# LEDs_Switches.net
KiCad netlist of a schematic drawn in Altium Designer
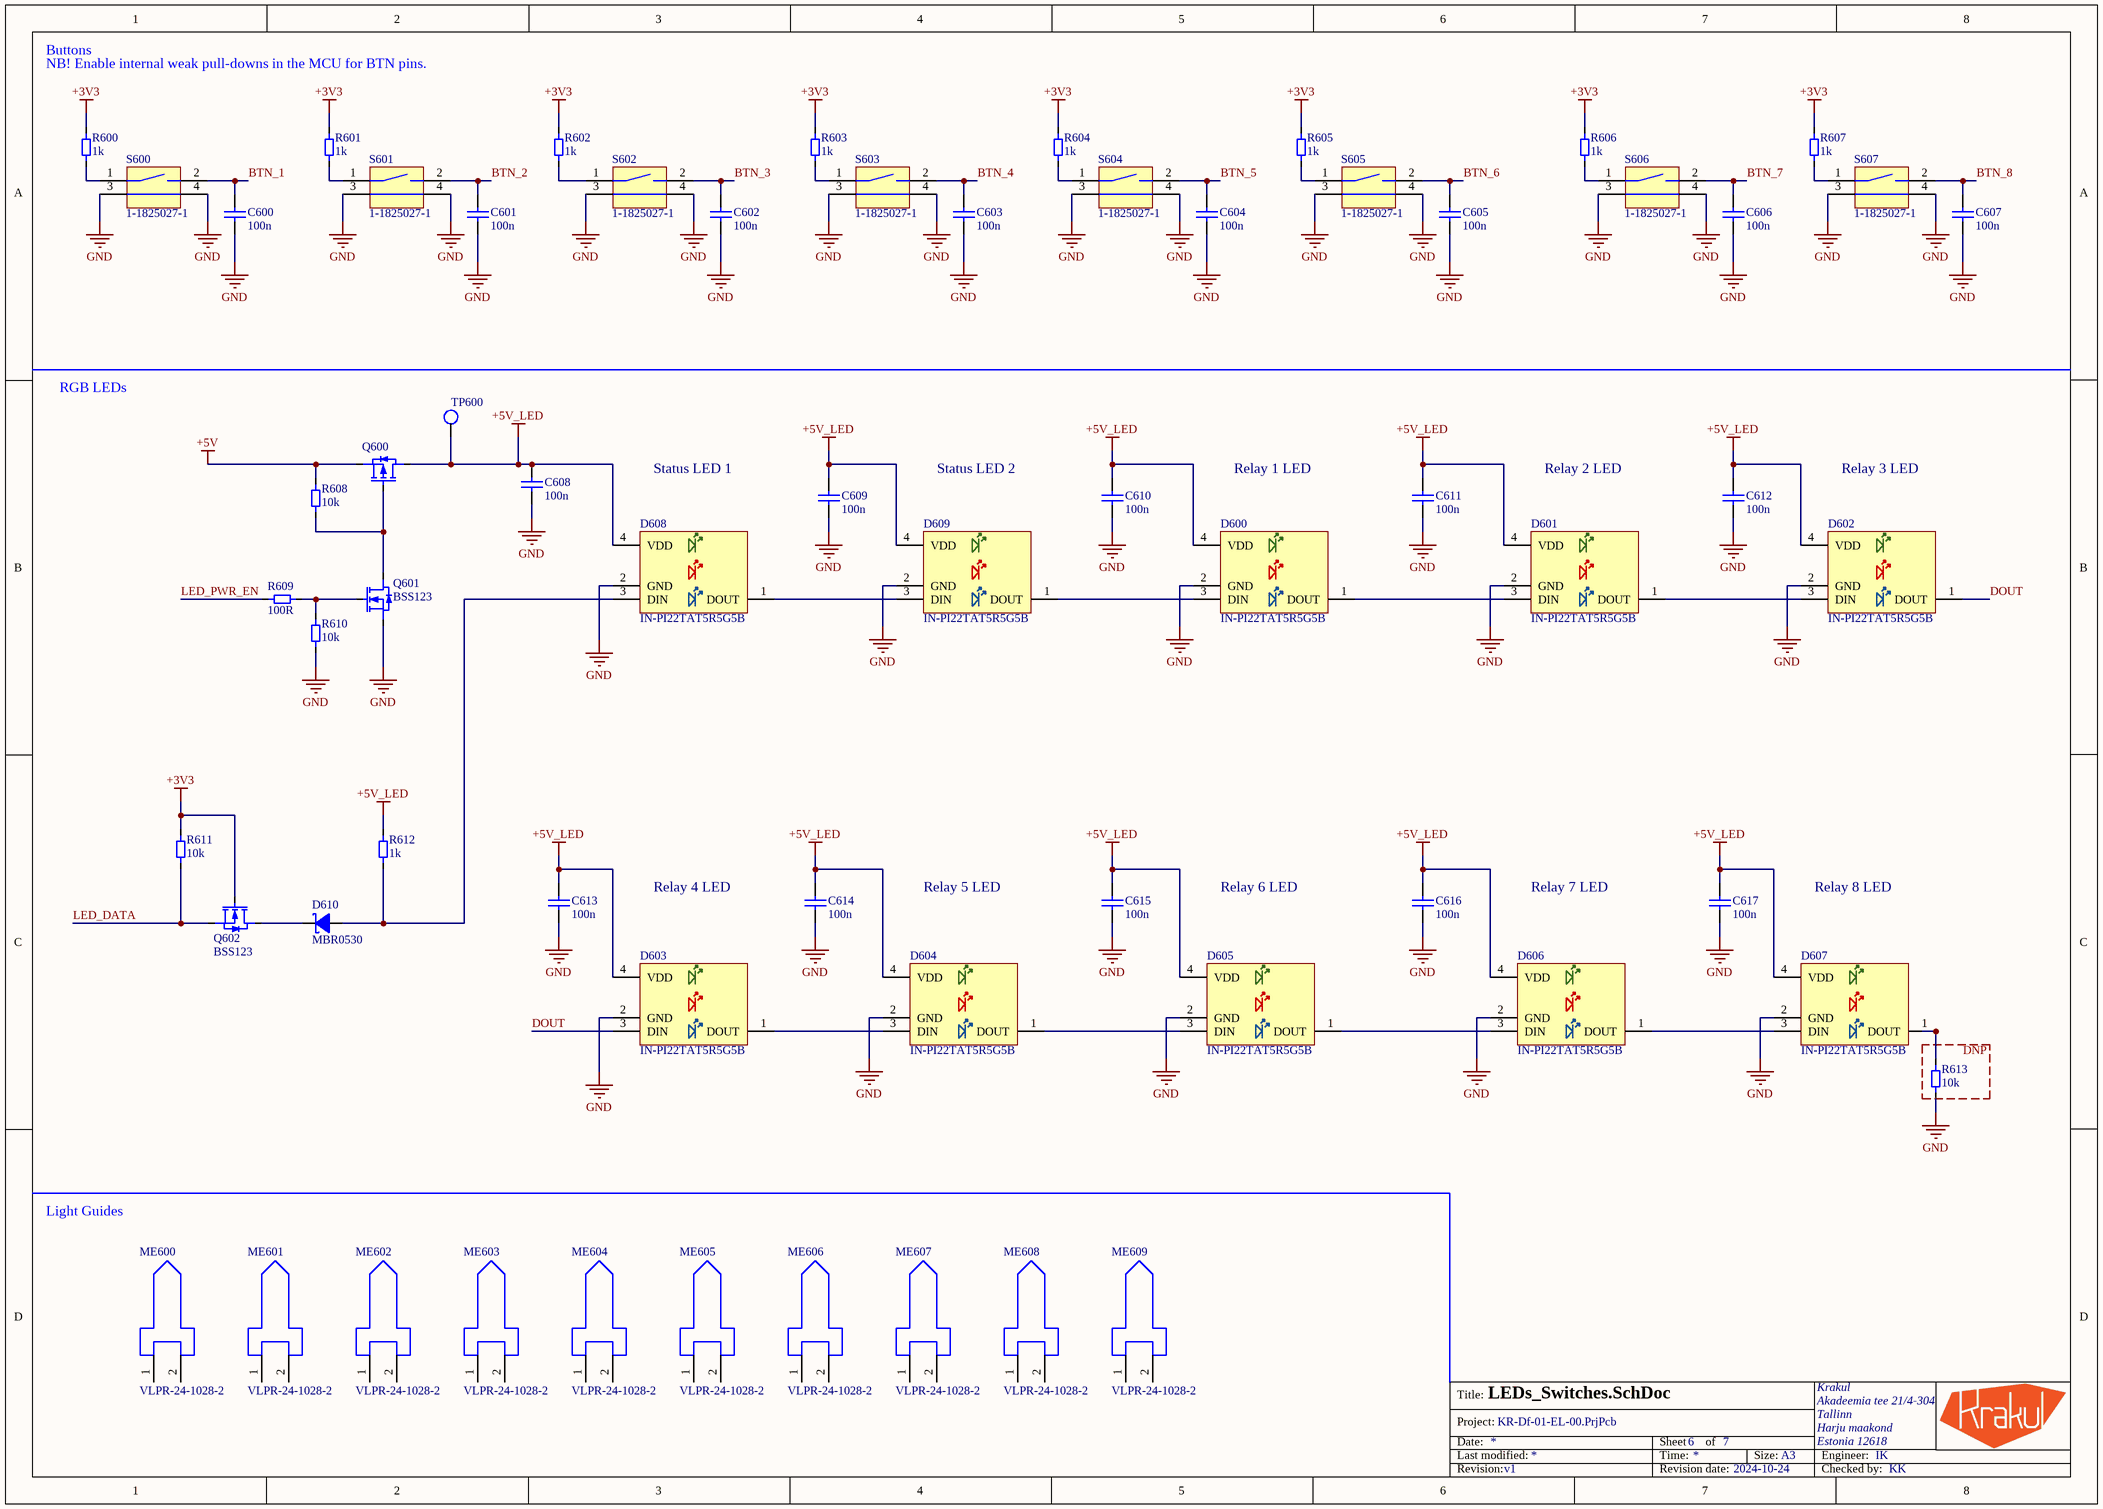
[diagram p0: LEDs_Switches.SchDoc]

(export (version "E")
  (design (tool "Eeschema 10.0.6"))
  (components
    (comp (ref "C600")
      (value "100n")
      (footprint "MLCC_0402_M")
      (description "MLCC, 0402, 100n, 10%, 10V, X5R")
      (fields (field (name "TOLERANCE") "10%") (field (name "MANUFACTURER") "Any"))
      (libsource (lib "Krakul Vault") (part "CAPACITOR_NONPOL_IEC"))
    )
    (comp (ref "C601")
      (value "100n")
      (footprint "MLCC_0402_M")
      (description "MLCC, 0402, 100n, 10%, 10V, X5R")
      (fields (field (name "TOLERANCE") "10%") (field (name "MANUFACTURER") "Any"))
      (libsource (lib "Krakul Vault") (part "CAPACITOR_NONPOL_IEC"))
    )
    (comp (ref "C602")
      (value "100n")
      (footprint "MLCC_0402_M")
      (description "MLCC, 0402, 100n, 10%, 10V, X5R")
      (fields (field (name "TOLERANCE") "10%") (field (name "MANUFACTURER") "Any"))
      (libsource (lib "Krakul Vault") (part "CAPACITOR_NONPOL_IEC"))
    )
    (comp (ref "C603")
      (value "100n")
      (footprint "MLCC_0402_M")
      (description "MLCC, 0402, 100n, 10%, 10V, X5R")
      (fields (field (name "TOLERANCE") "10%") (field (name "MANUFACTURER") "Any"))
      (libsource (lib "Krakul Vault") (part "CAPACITOR_NONPOL_IEC"))
    )
    (comp (ref "C604")
      (value "100n")
      (footprint "MLCC_0402_M")
      (description "MLCC, 0402, 100n, 10%, 10V, X5R")
      (fields (field (name "TOLERANCE") "10%") (field (name "MANUFACTURER") "Any"))
      (libsource (lib "Krakul Vault") (part "CAPACITOR_NONPOL_IEC"))
    )
    (comp (ref "C605")
      (value "100n")
      (footprint "MLCC_0402_M")
      (description "MLCC, 0402, 100n, 10%, 10V, X5R")
      (fields (field (name "TOLERANCE") "10%") (field (name "MANUFACTURER") "Any"))
      (libsource (lib "Krakul Vault") (part "CAPACITOR_NONPOL_IEC"))
    )
    (comp (ref "C606")
      (value "100n")
      (footprint "MLCC_0402_M")
      (description "MLCC, 0402, 100n, 10%, 10V, X5R")
      (fields (field (name "TOLERANCE") "10%") (field (name "MANUFACTURER") "Any"))
      (libsource (lib "Krakul Vault") (part "CAPACITOR_NONPOL_IEC"))
    )
    (comp (ref "C607")
      (value "100n")
      (footprint "MLCC_0402_M")
      (description "MLCC, 0402, 100n, 10%, 10V, X5R")
      (fields (field (name "TOLERANCE") "10%") (field (name "MANUFACTURER") "Any"))
      (libsource (lib "Krakul Vault") (part "CAPACITOR_NONPOL_IEC"))
    )
    (comp (ref "C608")
      (value "100n")
      (footprint "MLCC_0402_M")
      (description "MLCC, 0402, 100n, 10%, 10V, X5R")
      (fields (field (name "TOLERANCE") "10%") (field (name "MANUFACTURER") "Any"))
      (libsource (lib "Krakul Vault") (part "CAPACITOR_NONPOL_IEC"))
    )
    (comp (ref "C609")
      (value "100n")
      (footprint "MLCC_0402_M")
      (description "MLCC, 0402, 100n, 10%, 10V, X5R")
      (fields (field (name "TOLERANCE") "10%") (field (name "MANUFACTURER") "Any"))
      (libsource (lib "Krakul Vault") (part "CAPACITOR_NONPOL_IEC"))
    )
    (comp (ref "C610")
      (value "100n")
      (footprint "MLCC_0402_M")
      (description "MLCC, 0402, 100n, 10%, 10V, X5R")
      (fields (field (name "TOLERANCE") "10%") (field (name "MANUFACTURER") "Any"))
      (libsource (lib "Krakul Vault") (part "CAPACITOR_NONPOL_IEC"))
    )
    (comp (ref "C611")
      (value "100n")
      (footprint "MLCC_0402_M")
      (description "MLCC, 0402, 100n, 10%, 10V, X5R")
      (fields (field (name "TOLERANCE") "10%") (field (name "MANUFACTURER") "Any"))
      (libsource (lib "Krakul Vault") (part "CAPACITOR_NONPOL_IEC"))
    )
    (comp (ref "C612")
      (value "100n")
      (footprint "MLCC_0402_M")
      (description "MLCC, 0402, 100n, 10%, 10V, X5R")
      (fields (field (name "TOLERANCE") "10%") (field (name "MANUFACTURER") "Any"))
      (libsource (lib "Krakul Vault") (part "CAPACITOR_NONPOL_IEC"))
    )
    (comp (ref "C613")
      (value "100n")
      (footprint "MLCC_0402_M")
      (description "MLCC, 0402, 100n, 10%, 10V, X5R")
      (fields (field (name "TOLERANCE") "10%") (field (name "MANUFACTURER") "Any"))
      (libsource (lib "Krakul Vault") (part "CAPACITOR_NONPOL_IEC"))
    )
    (comp (ref "C614")
      (value "100n")
      (footprint "MLCC_0402_M")
      (description "MLCC, 0402, 100n, 10%, 10V, X5R")
      (fields (field (name "TOLERANCE") "10%") (field (name "MANUFACTURER") "Any"))
      (libsource (lib "Krakul Vault") (part "CAPACITOR_NONPOL_IEC"))
    )
    (comp (ref "C615")
      (value "100n")
      (footprint "MLCC_0402_M")
      (description "MLCC, 0402, 100n, 10%, 10V, X5R")
      (fields (field (name "TOLERANCE") "10%") (field (name "MANUFACTURER") "Any"))
      (libsource (lib "Krakul Vault") (part "CAPACITOR_NONPOL_IEC"))
    )
    (comp (ref "C616")
      (value "100n")
      (footprint "MLCC_0402_M")
      (description "MLCC, 0402, 100n, 10%, 10V, X5R")
      (fields (field (name "TOLERANCE") "10%") (field (name "MANUFACTURER") "Any"))
      (libsource (lib "Krakul Vault") (part "CAPACITOR_NONPOL_IEC"))
    )
    (comp (ref "C617")
      (value "100n")
      (footprint "MLCC_0402_M")
      (description "MLCC, 0402, 100n, 10%, 10V, X5R")
      (fields (field (name "TOLERANCE") "10%") (field (name "MANUFACTURER") "Any"))
      (libsource (lib "Krakul Vault") (part "CAPACITOR_NONPOL_IEC"))
    )
    (comp (ref "D600")
      (value "IN-PI22TAT5R5G5B")
      (footprint "IN-PI22TAT5R5G5B")
      (description "RGB LED, Discrete, Serial PWM(1Wire)")
      (fields (field (name "MANUFACTURER") "Inolux"))
      (libsource (lib "Krakul Vault") (part "IN-PI22TAT5R5G5B"))
    )
    (comp (ref "D601")
      (value "IN-PI22TAT5R5G5B")
      (footprint "IN-PI22TAT5R5G5B")
      (description "RGB LED, Discrete, Serial PWM(1Wire)")
      (fields (field (name "MANUFACTURER") "Inolux"))
      (libsource (lib "Krakul Vault") (part "IN-PI22TAT5R5G5B"))
    )
    (comp (ref "D602")
      (value "IN-PI22TAT5R5G5B")
      (footprint "IN-PI22TAT5R5G5B")
      (description "RGB LED, Discrete, Serial PWM(1Wire)")
      (fields (field (name "MANUFACTURER") "Inolux"))
      (libsource (lib "Krakul Vault") (part "IN-PI22TAT5R5G5B"))
    )
    (comp (ref "D603")
      (value "IN-PI22TAT5R5G5B")
      (footprint "IN-PI22TAT5R5G5B")
      (description "RGB LED, Discrete, Serial PWM(1Wire)")
      (fields (field (name "MANUFACTURER") "Inolux"))
      (libsource (lib "Krakul Vault") (part "IN-PI22TAT5R5G5B"))
    )
    (comp (ref "D604")
      (value "IN-PI22TAT5R5G5B")
      (footprint "IN-PI22TAT5R5G5B")
      (description "RGB LED, Discrete, Serial PWM(1Wire)")
      (fields (field (name "MANUFACTURER") "Inolux"))
      (libsource (lib "Krakul Vault") (part "IN-PI22TAT5R5G5B"))
    )
    (comp (ref "D605")
      (value "IN-PI22TAT5R5G5B")
      (footprint "IN-PI22TAT5R5G5B")
      (description "RGB LED, Discrete, Serial PWM(1Wire)")
      (fields (field (name "MANUFACTURER") "Inolux"))
      (libsource (lib "Krakul Vault") (part "IN-PI22TAT5R5G5B"))
    )
    (comp (ref "D606")
      (value "IN-PI22TAT5R5G5B")
      (footprint "IN-PI22TAT5R5G5B")
      (description "RGB LED, Discrete, Serial PWM(1Wire)")
      (fields (field (name "MANUFACTURER") "Inolux"))
      (libsource (lib "Krakul Vault") (part "IN-PI22TAT5R5G5B"))
    )
    (comp (ref "D607")
      (value "IN-PI22TAT5R5G5B")
      (footprint "IN-PI22TAT5R5G5B")
      (description "RGB LED, Discrete, Serial PWM(1Wire)")
      (fields (field (name "MANUFACTURER") "Inolux"))
      (libsource (lib "Krakul Vault") (part "IN-PI22TAT5R5G5B"))
    )
    (comp (ref "D608")
      (value "IN-PI22TAT5R5G5B")
      (footprint "IN-PI22TAT5R5G5B")
      (description "RGB LED, Discrete, Serial PWM(1Wire)")
      (fields (field (name "MANUFACTURER") "Inolux"))
      (libsource (lib "Krakul Vault") (part "IN-PI22TAT5R5G5B"))
    )
    (comp (ref "D609")
      (value "IN-PI22TAT5R5G5B")
      (footprint "IN-PI22TAT5R5G5B")
      (description "RGB LED, Discrete, Serial PWM(1Wire)")
      (fields (field (name "MANUFACTURER") "Inolux"))
      (libsource (lib "Krakul Vault") (part "IN-PI22TAT5R5G5B"))
    )
    (comp (ref "D610")
      (value "MBR0530")
      (footprint "SOD-123")
      (description "Diode Schottky 30V 500mA Surface Mount SOD-123")
      (fields (field (name "MANUFACTURER") "ON Semiconductor"))
      (libsource (lib "Krakul Vault") (part "Schottky generic 2 pins"))
    )
    (comp (ref "ME600")
      (value "VLPR-24-1028-2")
      (footprint "VLPR-24-1028-2-Footprint-1")
      (description "Light Pipe, Rigid, Vertical, Board Mount, Smd Led, 1.028 In., 4 Mm X 2 Mm Rectangular Face")
      (fields (field (name "MANUFACTURER") "Bivar"))
      (libsource (lib "Krakul Vault") (part "VLPR-24-1028-2-Symbol-1"))
    )
    (comp (ref "ME601")
      (value "VLPR-24-1028-2")
      (footprint "VLPR-24-1028-2-Footprint-1")
      (description "Light Pipe, Rigid, Vertical, Board Mount, Smd Led, 1.028 In., 4 Mm X 2 Mm Rectangular Face")
      (fields (field (name "MANUFACTURER") "Bivar"))
      (libsource (lib "Krakul Vault") (part "VLPR-24-1028-2-Symbol-1"))
    )
    (comp (ref "ME602")
      (value "VLPR-24-1028-2")
      (footprint "VLPR-24-1028-2-Footprint-1")
      (description "Light Pipe, Rigid, Vertical, Board Mount, Smd Led, 1.028 In., 4 Mm X 2 Mm Rectangular Face")
      (fields (field (name "MANUFACTURER") "Bivar"))
      (libsource (lib "Krakul Vault") (part "VLPR-24-1028-2-Symbol-1"))
    )
    (comp (ref "ME603")
      (value "VLPR-24-1028-2")
      (footprint "VLPR-24-1028-2-Footprint-1")
      (description "Light Pipe, Rigid, Vertical, Board Mount, Smd Led, 1.028 In., 4 Mm X 2 Mm Rectangular Face")
      (fields (field (name "MANUFACTURER") "Bivar"))
      (libsource (lib "Krakul Vault") (part "VLPR-24-1028-2-Symbol-1"))
    )
    (comp (ref "ME604")
      (value "VLPR-24-1028-2")
      (footprint "VLPR-24-1028-2-Footprint-1")
      (description "Light Pipe, Rigid, Vertical, Board Mount, Smd Led, 1.028 In., 4 Mm X 2 Mm Rectangular Face")
      (fields (field (name "MANUFACTURER") "Bivar"))
      (libsource (lib "Krakul Vault") (part "VLPR-24-1028-2-Symbol-1"))
    )
    (comp (ref "ME605")
      (value "VLPR-24-1028-2")
      (footprint "VLPR-24-1028-2-Footprint-1")
      (description "Light Pipe, Rigid, Vertical, Board Mount, Smd Led, 1.028 In., 4 Mm X 2 Mm Rectangular Face")
      (fields (field (name "MANUFACTURER") "Bivar"))
      (libsource (lib "Krakul Vault") (part "VLPR-24-1028-2-Symbol-1"))
    )
    (comp (ref "ME606")
      (value "VLPR-24-1028-2")
      (footprint "VLPR-24-1028-2-Footprint-1")
      (description "Light Pipe, Rigid, Vertical, Board Mount, Smd Led, 1.028 In., 4 Mm X 2 Mm Rectangular Face")
      (fields (field (name "MANUFACTURER") "Bivar"))
      (libsource (lib "Krakul Vault") (part "VLPR-24-1028-2-Symbol-1"))
    )
    (comp (ref "ME607")
      (value "VLPR-24-1028-2")
      (footprint "VLPR-24-1028-2-Footprint-1")
      (description "Light Pipe, Rigid, Vertical, Board Mount, Smd Led, 1.028 In., 4 Mm X 2 Mm Rectangular Face")
      (fields (field (name "MANUFACTURER") "Bivar"))
      (libsource (lib "Krakul Vault") (part "VLPR-24-1028-2-Symbol-1"))
    )
    (comp (ref "ME608")
      (value "VLPR-24-1028-2")
      (footprint "VLPR-24-1028-2-Footprint-1")
      (description "Light Pipe, Rigid, Vertical, Board Mount, Smd Led, 1.028 In., 4 Mm X 2 Mm Rectangular Face")
      (fields (field (name "MANUFACTURER") "Bivar"))
      (libsource (lib "Krakul Vault") (part "VLPR-24-1028-2-Symbol-1"))
    )
    (comp (ref "ME609")
      (value "VLPR-24-1028-2")
      (footprint "VLPR-24-1028-2-Footprint-1")
      (description "Light Pipe, Rigid, Vertical, Board Mount, Smd Led, 1.028 In., 4 Mm X 2 Mm Rectangular Face")
      (fields (field (name "MANUFACTURER") "Bivar"))
      (libsource (lib "Krakul Vault") (part "VLPR-24-1028-2-Symbol-1"))
    )
    (comp (ref "Q600")
      (value "DMG2305UX-13")
      (footprint "SOT-23-3")
      (description "P-Channel 20V 4.2A (Ta) 1.4W (Ta) Surface Mount SOT-23")
      (fields (field (name "MANUFACTURER") "Diodes Incorporated"))
      (libsource (lib "Krakul Vault") (part "P-CH MOSFET 3-pin SOT"))
    )
    (comp (ref "Q601")
      (value "BSS123")
      (footprint "SOT-23-3")
      (description "MOSFET N-CH 100V 170MA SOT-23")
      (fields (field (name "MANUFACTURER") "ON Semiconductor") (field (name "VOLTAGE") "100V"))
      (libsource (lib "Krakul Vault") (part "N-CH MOSFET 3-pin SOT"))
    )
    (comp (ref "Q602")
      (value "BSS123")
      (footprint "SOT-23-3")
      (description "MOSFET N-CH 100V 170MA SOT-23")
      (fields (field (name "MANUFACTURER") "ON Semiconductor") (field (name "VOLTAGE") "100V"))
      (libsource (lib "Krakul Vault") (part "N-CH MOSFET 3-pin SOT"))
    )
    (comp (ref "R600")
      (value "1k")
      (footprint "Resistor_0603_M")
      (description "Resistor, 0603, 1k, 0.1%, 1/16W")
      (fields (field (name "MANUFACTURER") "Any"))
      (libsource (lib "Krakul Vault") (part "RESISTOR_GENERIC_IEC"))
    )
    (comp (ref "R601")
      (value "1k")
      (footprint "Resistor_0603_M")
      (description "Resistor, 0603, 1k, 0.1%, 1/16W")
      (fields (field (name "MANUFACTURER") "Any"))
      (libsource (lib "Krakul Vault") (part "RESISTOR_GENERIC_IEC"))
    )
    (comp (ref "R602")
      (value "1k")
      (footprint "Resistor_0603_M")
      (description "Resistor, 0603, 1k, 0.1%, 1/16W")
      (fields (field (name "MANUFACTURER") "Any"))
      (libsource (lib "Krakul Vault") (part "RESISTOR_GENERIC_IEC"))
    )
    (comp (ref "R603")
      (value "1k")
      (footprint "Resistor_0603_M")
      (description "Resistor, 0603, 1k, 0.1%, 1/16W")
      (fields (field (name "MANUFACTURER") "Any"))
      (libsource (lib "Krakul Vault") (part "RESISTOR_GENERIC_IEC"))
    )
    (comp (ref "R604")
      (value "1k")
      (footprint "Resistor_0603_M")
      (description "Resistor, 0603, 1k, 0.1%, 1/16W")
      (fields (field (name "MANUFACTURER") "Any"))
      (libsource (lib "Krakul Vault") (part "RESISTOR_GENERIC_IEC"))
    )
    (comp (ref "R605")
      (value "1k")
      (footprint "Resistor_0603_M")
      (description "Resistor, 0603, 1k, 0.1%, 1/16W")
      (fields (field (name "MANUFACTURER") "Any"))
      (libsource (lib "Krakul Vault") (part "RESISTOR_GENERIC_IEC"))
    )
    (comp (ref "R606")
      (value "1k")
      (footprint "Resistor_0603_M")
      (description "Resistor, 0603, 1k, 0.1%, 1/16W")
      (fields (field (name "MANUFACTURER") "Any"))
      (libsource (lib "Krakul Vault") (part "RESISTOR_GENERIC_IEC"))
    )
    (comp (ref "R607")
      (value "1k")
      (footprint "Resistor_0603_M")
      (description "Resistor, 0603, 1k, 0.1%, 1/16W")
      (fields (field (name "MANUFACTURER") "Any"))
      (libsource (lib "Krakul Vault") (part "RESISTOR_GENERIC_IEC"))
    )
    (comp (ref "R608")
      (value "10k")
      (footprint "Resistor_0603_M")
      (description "Resistor, 0603, 10k, 1%, 1/10W")
      (fields (field (name "MANUFACTURER") "Any") (field (name "TOLERANCE") "1%"))
      (libsource (lib "Krakul Vault") (part "RESISTOR_GENERIC_IEC"))
    )
    (comp (ref "R609")
      (value "100R")
      (footprint "Resistor_0603_M")
      (description "Resistor, 0603, 100R, 1%, 1/10W")
      (fields (field (name "TOLERANCE") "1%") (field (name "POWER") "100mW"))
      (libsource (lib "Krakul Vault") (part "RESISTOR_GENERIC_IEC"))
    )
    (comp (ref "R610")
      (value "10k")
      (footprint "Resistor_0603_M")
      (description "Resistor, 0603, 10k, 1%, 1/10W")
      (fields (field (name "MANUFACTURER") "Any") (field (name "TOLERANCE") "1%"))
      (libsource (lib "Krakul Vault") (part "RESISTOR_GENERIC_IEC"))
    )
    (comp (ref "R611")
      (value "10k")
      (footprint "Resistor_0603_M")
      (description "Resistor, 0603, 10k, 1%, 1/10W")
      (fields (field (name "MANUFACTURER") "Any") (field (name "TOLERANCE") "1%"))
      (libsource (lib "Krakul Vault") (part "RESISTOR_GENERIC_IEC"))
    )
    (comp (ref "R612")
      (value "1k")
      (footprint "Resistor_0603_M")
      (description "Resistor, 0603, 1k, 0.1%, 1/16W")
      (fields (field (name "MANUFACTURER") "Any"))
      (libsource (lib "Krakul Vault") (part "RESISTOR_GENERIC_IEC"))
    )
    (comp (ref "R613")
      (value "10k")
      (footprint "Resistor_0603_M")
      (description "Resistor, 0603, 10k, 1%, 1/10W")
      (fields (field (name "MANUFACTURER") "Any") (field (name "TOLERANCE") "1%"))
      (libsource (lib "Krakul Vault") (part "RESISTOR_GENERIC_IEC"))
    )
    (comp (ref "S600")
      (value "1-1825027-1")
      (footprint "1-1825027-1-Footprint-1")
      (description "Switch Push Button OFF (ON) SPST Round Button 0.05A 24VDC Momentary Contact PC Pins Thru-Hole")
      (fields (field (name "MANUFACTURER") "TE"))
      (libsource (lib "Krakul Vault") (part "1-1825027-1-Symbol-1"))
    )
    (comp (ref "S601")
      (value "1-1825027-1")
      (footprint "1-1825027-1-Footprint-1")
      (description "Switch Push Button OFF (ON) SPST Round Button 0.05A 24VDC Momentary Contact PC Pins Thru-Hole")
      (fields (field (name "MANUFACTURER") "TE"))
      (libsource (lib "Krakul Vault") (part "1-1825027-1-Symbol-1"))
    )
    (comp (ref "S602")
      (value "1-1825027-1")
      (footprint "1-1825027-1-Footprint-1")
      (description "Switch Push Button OFF (ON) SPST Round Button 0.05A 24VDC Momentary Contact PC Pins Thru-Hole")
      (fields (field (name "MANUFACTURER") "TE"))
      (libsource (lib "Krakul Vault") (part "1-1825027-1-Symbol-1"))
    )
    (comp (ref "S603")
      (value "1-1825027-1")
      (footprint "1-1825027-1-Footprint-1")
      (description "Switch Push Button OFF (ON) SPST Round Button 0.05A 24VDC Momentary Contact PC Pins Thru-Hole")
      (fields (field (name "MANUFACTURER") "TE"))
      (libsource (lib "Krakul Vault") (part "1-1825027-1-Symbol-1"))
    )
    (comp (ref "S604")
      (value "1-1825027-1")
      (footprint "1-1825027-1-Footprint-1")
      (description "Switch Push Button OFF (ON) SPST Round Button 0.05A 24VDC Momentary Contact PC Pins Thru-Hole")
      (fields (field (name "MANUFACTURER") "TE"))
      (libsource (lib "Krakul Vault") (part "1-1825027-1-Symbol-1"))
    )
    (comp (ref "S605")
      (value "1-1825027-1")
      (footprint "1-1825027-1-Footprint-1")
      (description "Switch Push Button OFF (ON) SPST Round Button 0.05A 24VDC Momentary Contact PC Pins Thru-Hole")
      (fields (field (name "MANUFACTURER") "TE"))
      (libsource (lib "Krakul Vault") (part "1-1825027-1-Symbol-1"))
    )
    (comp (ref "S606")
      (value "1-1825027-1")
      (footprint "1-1825027-1-Footprint-1")
      (description "Switch Push Button OFF (ON) SPST Round Button 0.05A 24VDC Momentary Contact PC Pins Thru-Hole")
      (fields (field (name "MANUFACTURER") "TE"))
      (libsource (lib "Krakul Vault") (part "1-1825027-1-Symbol-1"))
    )
    (comp (ref "S607")
      (value "1-1825027-1")
      (footprint "1-1825027-1-Footprint-1")
      (description "Switch Push Button OFF (ON) SPST Round Button 0.05A 24VDC Momentary Contact PC Pins Thru-Hole")
      (fields (field (name "MANUFACTURER") "TE"))
      (libsource (lib "Krakul Vault") (part "1-1825027-1-Symbol-1"))
    )
    (comp (ref "TP600")
      (value "Testpoint 1mm")
      (footprint "Testpoint 1mm")
      (libsource (lib "Krakul Vault") (part "Testpoint"))
    )
  )
  (nets
    (net (code "1") (name "+3V3") (class "Default")
      (node (ref "Q602") (pin "1") (pinfunction "G_1") (pintype "passive"))
      (node (ref "R600") (pin "2") (pinfunction "2_2") (pintype "passive"))
      (node (ref "R601") (pin "2") (pinfunction "2_2") (pintype "passive"))
      (node (ref "R602") (pin "2") (pinfunction "2_2") (pintype "passive"))
      (node (ref "R603") (pin "2") (pinfunction "2_2") (pintype "passive"))
      (node (ref "R604") (pin "2") (pinfunction "2_2") (pintype "passive"))
      (node (ref "R605") (pin "2") (pinfunction "2_2") (pintype "passive"))
      (node (ref "R606") (pin "2") (pinfunction "2_2") (pintype "passive"))
      (node (ref "R607") (pin "2") (pinfunction "2_2") (pintype "passive"))
      (node (ref "R611") (pin "2") (pinfunction "2_2") (pintype "passive"))
    )
    (net (code "2") (name "+5V") (class "Default")
      (node (ref "Q600") (pin "2") (pinfunction "S_2") (pintype "passive"))
      (node (ref "R608") (pin "2") (pinfunction "2_2") (pintype "passive"))
    )
    (net (code "3") (name "+5V_LED") (class "Default")
      (node (ref "C608") (pin "2") (pinfunction "2_2") (pintype "passive"))
      (node (ref "C609") (pin "2") (pinfunction "2_2") (pintype "passive"))
      (node (ref "C610") (pin "2") (pinfunction "2_2") (pintype "passive"))
      (node (ref "C611") (pin "2") (pinfunction "2_2") (pintype "passive"))
      (node (ref "C612") (pin "2") (pinfunction "2_2") (pintype "passive"))
      (node (ref "C613") (pin "2") (pinfunction "2_2") (pintype "passive"))
      (node (ref "C614") (pin "2") (pinfunction "2_2") (pintype "passive"))
      (node (ref "C615") (pin "2") (pinfunction "2_2") (pintype "passive"))
      (node (ref "C616") (pin "2") (pinfunction "2_2") (pintype "passive"))
      (node (ref "C617") (pin "2") (pinfunction "2_2") (pintype "passive"))
      (node (ref "D600") (pin "4") (pinfunction "VDD_4") (pintype "passive"))
      (node (ref "D601") (pin "4") (pinfunction "VDD_4") (pintype "passive"))
      (node (ref "D602") (pin "4") (pinfunction "VDD_4") (pintype "passive"))
      (node (ref "D603") (pin "4") (pinfunction "VDD_4") (pintype "passive"))
      (node (ref "D604") (pin "4") (pinfunction "VDD_4") (pintype "passive"))
      (node (ref "D605") (pin "4") (pinfunction "VDD_4") (pintype "passive"))
      (node (ref "D606") (pin "4") (pinfunction "VDD_4") (pintype "passive"))
      (node (ref "D607") (pin "4") (pinfunction "VDD_4") (pintype "passive"))
      (node (ref "D608") (pin "4") (pinfunction "VDD_4") (pintype "passive"))
      (node (ref "D609") (pin "4") (pinfunction "VDD_4") (pintype "passive"))
      (node (ref "Q600") (pin "3") (pinfunction "D_3") (pintype "passive"))
      (node (ref "R612") (pin "2") (pinfunction "2_2") (pintype "passive"))
      (node (ref "TP600") (pin "1") (pinfunction "1_1") (pintype "passive"))
    )
    (net (code "4") (name "/BTN_1") (class "Default")
      (node (ref "C600") (pin "2") (pinfunction "2_2") (pintype "passive"))
      (node (ref "S600") (pin "2") (pinfunction "2_2") (pintype "passive"))
    )
    (net (code "5") (name "/BTN_2") (class "Default")
      (node (ref "C601") (pin "2") (pinfunction "2_2") (pintype "passive"))
      (node (ref "S601") (pin "2") (pinfunction "2_2") (pintype "passive"))
    )
    (net (code "6") (name "/BTN_3") (class "Default")
      (node (ref "C602") (pin "2") (pinfunction "2_2") (pintype "passive"))
      (node (ref "S602") (pin "2") (pinfunction "2_2") (pintype "passive"))
    )
    (net (code "7") (name "/BTN_4") (class "Default")
      (node (ref "C603") (pin "2") (pinfunction "2_2") (pintype "passive"))
      (node (ref "S603") (pin "2") (pinfunction "2_2") (pintype "passive"))
    )
    (net (code "8") (name "/BTN_5") (class "Default")
      (node (ref "C604") (pin "2") (pinfunction "2_2") (pintype "passive"))
      (node (ref "S604") (pin "2") (pinfunction "2_2") (pintype "passive"))
    )
    (net (code "9") (name "/BTN_6") (class "Default")
      (node (ref "C605") (pin "2") (pinfunction "2_2") (pintype "passive"))
      (node (ref "S605") (pin "2") (pinfunction "2_2") (pintype "passive"))
    )
    (net (code "10") (name "/BTN_7") (class "Default")
      (node (ref "C606") (pin "2") (pinfunction "2_2") (pintype "passive"))
      (node (ref "S606") (pin "2") (pinfunction "2_2") (pintype "passive"))
    )
    (net (code "11") (name "/BTN_8") (class "Default")
      (node (ref "C607") (pin "2") (pinfunction "2_2") (pintype "passive"))
      (node (ref "S607") (pin "2") (pinfunction "2_2") (pintype "passive"))
    )
    (net (code "12") (name "/DOUT") (class "Default")
      (node (ref "D602") (pin "1") (pinfunction "DOUT_1") (pintype "passive"))
      (node (ref "D603") (pin "3") (pinfunction "DIN_3") (pintype "passive"))
    )
    (net (code "13") (name "/LED_DATA") (class "Default")
      (node (ref "Q602") (pin "2") (pinfunction "S_2") (pintype "passive"))
      (node (ref "R611") (pin "1") (pinfunction "1_1") (pintype "passive"))
    )
    (net (code "14") (name "/LED_PWR_EN") (class "Default")
      (node (ref "R609") (pin "1") (pinfunction "1_1") (pintype "passive"))
    )
    (net (code "15") (name "GND") (class "Default")
      (node (ref "C600") (pin "1") (pinfunction "1_1") (pintype "passive"))
      (node (ref "C601") (pin "1") (pinfunction "1_1") (pintype "passive"))
      (node (ref "C602") (pin "1") (pinfunction "1_1") (pintype "passive"))
      (node (ref "C603") (pin "1") (pinfunction "1_1") (pintype "passive"))
      (node (ref "C604") (pin "1") (pinfunction "1_1") (pintype "passive"))
      (node (ref "C605") (pin "1") (pinfunction "1_1") (pintype "passive"))
      (node (ref "C606") (pin "1") (pinfunction "1_1") (pintype "passive"))
      (node (ref "C607") (pin "1") (pinfunction "1_1") (pintype "passive"))
      (node (ref "C608") (pin "1") (pinfunction "1_1") (pintype "passive"))
      (node (ref "C609") (pin "1") (pinfunction "1_1") (pintype "passive"))
      (node (ref "C610") (pin "1") (pinfunction "1_1") (pintype "passive"))
      (node (ref "C611") (pin "1") (pinfunction "1_1") (pintype "passive"))
      (node (ref "C612") (pin "1") (pinfunction "1_1") (pintype "passive"))
      (node (ref "C613") (pin "1") (pinfunction "1_1") (pintype "passive"))
      (node (ref "C614") (pin "1") (pinfunction "1_1") (pintype "passive"))
      (node (ref "C615") (pin "1") (pinfunction "1_1") (pintype "passive"))
      (node (ref "C616") (pin "1") (pinfunction "1_1") (pintype "passive"))
      (node (ref "C617") (pin "1") (pinfunction "1_1") (pintype "passive"))
      (node (ref "D600") (pin "2") (pinfunction "GND_2") (pintype "passive"))
      (node (ref "D601") (pin "2") (pinfunction "GND_2") (pintype "passive"))
      (node (ref "D602") (pin "2") (pinfunction "GND_2") (pintype "passive"))
      (node (ref "D603") (pin "2") (pinfunction "GND_2") (pintype "passive"))
      (node (ref "D604") (pin "2") (pinfunction "GND_2") (pintype "passive"))
      (node (ref "D605") (pin "2") (pinfunction "GND_2") (pintype "passive"))
      (node (ref "D606") (pin "2") (pinfunction "GND_2") (pintype "passive"))
      (node (ref "D607") (pin "2") (pinfunction "GND_2") (pintype "passive"))
      (node (ref "D608") (pin "2") (pinfunction "GND_2") (pintype "passive"))
      (node (ref "D609") (pin "2") (pinfunction "GND_2") (pintype "passive"))
      (node (ref "Q601") (pin "2") (pinfunction "S_2") (pintype "passive"))
      (node (ref "R610") (pin "1") (pinfunction "1_1") (pintype "passive"))
      (node (ref "R613") (pin "1") (pinfunction "1_1") (pintype "passive"))
      (node (ref "S600") (pin "3") (pinfunction "3_3") (pintype "passive"))
      (node (ref "S600") (pin "4") (pinfunction "4_4") (pintype "passive"))
      (node (ref "S601") (pin "3") (pinfunction "3_3") (pintype "passive"))
      (node (ref "S601") (pin "4") (pinfunction "4_4") (pintype "passive"))
      (node (ref "S602") (pin "3") (pinfunction "3_3") (pintype "passive"))
      (node (ref "S602") (pin "4") (pinfunction "4_4") (pintype "passive"))
      (node (ref "S603") (pin "3") (pinfunction "3_3") (pintype "passive"))
      (node (ref "S603") (pin "4") (pinfunction "4_4") (pintype "passive"))
      (node (ref "S604") (pin "3") (pinfunction "3_3") (pintype "passive"))
      (node (ref "S604") (pin "4") (pinfunction "4_4") (pintype "passive"))
      (node (ref "S605") (pin "3") (pinfunction "3_3") (pintype "passive"))
      (node (ref "S605") (pin "4") (pinfunction "4_4") (pintype "passive"))
      (node (ref "S606") (pin "3") (pinfunction "3_3") (pintype "passive"))
      (node (ref "S606") (pin "4") (pinfunction "4_4") (pintype "passive"))
      (node (ref "S607") (pin "3") (pinfunction "3_3") (pintype "passive"))
      (node (ref "S607") (pin "4") (pinfunction "4_4") (pintype "passive"))
    )
    (net (code "16") (name "Net-(D600-DIN)") (class "Default")
      (node (ref "D600") (pin "3") (pinfunction "DIN_3") (pintype "passive"))
      (node (ref "D609") (pin "1") (pinfunction "DOUT_1") (pintype "passive"))
    )
    (net (code "17") (name "Net-(D600-DOUT)") (class "Default")
      (node (ref "D600") (pin "1") (pinfunction "DOUT_1") (pintype "passive"))
      (node (ref "D601") (pin "3") (pinfunction "DIN_3") (pintype "passive"))
    )
    (net (code "18") (name "Net-(D601-DOUT)") (class "Default")
      (node (ref "D601") (pin "1") (pinfunction "DOUT_1") (pintype "passive"))
      (node (ref "D602") (pin "3") (pinfunction "DIN_3") (pintype "passive"))
    )
    (net (code "19") (name "Net-(D603-DOUT)") (class "Default")
      (node (ref "D603") (pin "1") (pinfunction "DOUT_1") (pintype "passive"))
      (node (ref "D604") (pin "3") (pinfunction "DIN_3") (pintype "passive"))
    )
    (net (code "20") (name "Net-(D604-DOUT)") (class "Default")
      (node (ref "D604") (pin "1") (pinfunction "DOUT_1") (pintype "passive"))
      (node (ref "D605") (pin "3") (pinfunction "DIN_3") (pintype "passive"))
    )
    (net (code "21") (name "Net-(D605-DOUT)") (class "Default")
      (node (ref "D605") (pin "1") (pinfunction "DOUT_1") (pintype "passive"))
      (node (ref "D606") (pin "3") (pinfunction "DIN_3") (pintype "passive"))
    )
    (net (code "22") (name "Net-(D606-DOUT)") (class "Default")
      (node (ref "D606") (pin "1") (pinfunction "DOUT_1") (pintype "passive"))
      (node (ref "D607") (pin "3") (pinfunction "DIN_3") (pintype "passive"))
    )
    (net (code "23") (name "Net-(D607-DOUT)") (class "Default")
      (node (ref "D607") (pin "1") (pinfunction "DOUT_1") (pintype "passive"))
      (node (ref "R613") (pin "2") (pinfunction "2_2") (pintype "passive"))
    )
    (net (code "24") (name "Net-(D608-DIN)") (class "Default")
      (node (ref "D608") (pin "3") (pinfunction "DIN_3") (pintype "passive"))
      (node (ref "D610") (pin "2") (pinfunction "A_2") (pintype "passive"))
      (node (ref "R612") (pin "1") (pinfunction "1_1") (pintype "passive"))
    )
    (net (code "25") (name "Net-(D608-DOUT)") (class "Default")
      (node (ref "D608") (pin "1") (pinfunction "DOUT_1") (pintype "passive"))
      (node (ref "D609") (pin "3") (pinfunction "DIN_3") (pintype "passive"))
    )
    (net (code "26") (name "Net-(D610-C)") (class "Default")
      (node (ref "D610") (pin "1") (pinfunction "C_1") (pintype "passive"))
      (node (ref "Q602") (pin "3") (pinfunction "D_3") (pintype "passive"))
    )
    (net (code "27") (name "Net-(Q600-G)") (class "Default")
      (node (ref "Q600") (pin "1") (pinfunction "G_1") (pintype "passive"))
      (node (ref "Q601") (pin "3") (pinfunction "D_3") (pintype "passive"))
      (node (ref "R608") (pin "1") (pinfunction "1_1") (pintype "passive"))
    )
    (net (code "28") (name "Net-(Q601-G)") (class "Default")
      (node (ref "Q601") (pin "1") (pinfunction "G_1") (pintype "passive"))
      (node (ref "R609") (pin "2") (pinfunction "2_2") (pintype "passive"))
      (node (ref "R610") (pin "2") (pinfunction "2_2") (pintype "passive"))
    )
    (net (code "29") (name "Net-(R600-Pad1)") (class "Default")
      (node (ref "R600") (pin "1") (pinfunction "1_1") (pintype "passive"))
      (node (ref "S600") (pin "1") (pinfunction "1_1") (pintype "passive"))
    )
    (net (code "30") (name "Net-(R601-Pad1)") (class "Default")
      (node (ref "R601") (pin "1") (pinfunction "1_1") (pintype "passive"))
      (node (ref "S601") (pin "1") (pinfunction "1_1") (pintype "passive"))
    )
    (net (code "31") (name "Net-(R602-Pad1)") (class "Default")
      (node (ref "R602") (pin "1") (pinfunction "1_1") (pintype "passive"))
      (node (ref "S602") (pin "1") (pinfunction "1_1") (pintype "passive"))
    )
    (net (code "32") (name "Net-(R603-Pad1)") (class "Default")
      (node (ref "R603") (pin "1") (pinfunction "1_1") (pintype "passive"))
      (node (ref "S603") (pin "1") (pinfunction "1_1") (pintype "passive"))
    )
    (net (code "33") (name "Net-(R604-Pad1)") (class "Default")
      (node (ref "R604") (pin "1") (pinfunction "1_1") (pintype "passive"))
      (node (ref "S604") (pin "1") (pinfunction "1_1") (pintype "passive"))
    )
    (net (code "34") (name "Net-(R605-Pad1)") (class "Default")
      (node (ref "R605") (pin "1") (pinfunction "1_1") (pintype "passive"))
      (node (ref "S605") (pin "1") (pinfunction "1_1") (pintype "passive"))
    )
    (net (code "35") (name "Net-(R606-Pad1)") (class "Default")
      (node (ref "R606") (pin "1") (pinfunction "1_1") (pintype "passive"))
      (node (ref "S606") (pin "1") (pinfunction "1_1") (pintype "passive"))
    )
    (net (code "36") (name "Net-(R607-Pad1)") (class "Default")
      (node (ref "R607") (pin "1") (pinfunction "1_1") (pintype "passive"))
      (node (ref "S607") (pin "1") (pinfunction "1_1") (pintype "passive"))
    )
    (net (code "37") (name "unconnected-(ME600-Pad1)") (class "Default")
      (node (ref "ME600") (pin "1") (pinfunction "1_1") (pintype "passive"))
    )
    (net (code "38") (name "unconnected-(ME600-Pad2)") (class "Default")
      (node (ref "ME600") (pin "2") (pinfunction "2_2") (pintype "passive"))
    )
    (net (code "39") (name "unconnected-(ME601-Pad1)") (class "Default")
      (node (ref "ME601") (pin "1") (pinfunction "1_1") (pintype "passive"))
    )
    (net (code "40") (name "unconnected-(ME601-Pad2)") (class "Default")
      (node (ref "ME601") (pin "2") (pinfunction "2_2") (pintype "passive"))
    )
    (net (code "41") (name "unconnected-(ME602-Pad1)") (class "Default")
      (node (ref "ME602") (pin "1") (pinfunction "1_1") (pintype "passive"))
    )
    (net (code "42") (name "unconnected-(ME602-Pad2)") (class "Default")
      (node (ref "ME602") (pin "2") (pinfunction "2_2") (pintype "passive"))
    )
    (net (code "43") (name "unconnected-(ME603-Pad1)") (class "Default")
      (node (ref "ME603") (pin "1") (pinfunction "1_1") (pintype "passive"))
    )
    (net (code "44") (name "unconnected-(ME603-Pad2)") (class "Default")
      (node (ref "ME603") (pin "2") (pinfunction "2_2") (pintype "passive"))
    )
    (net (code "45") (name "unconnected-(ME604-Pad1)") (class "Default")
      (node (ref "ME604") (pin "1") (pinfunction "1_1") (pintype "passive"))
    )
    (net (code "46") (name "unconnected-(ME604-Pad2)") (class "Default")
      (node (ref "ME604") (pin "2") (pinfunction "2_2") (pintype "passive"))
    )
    (net (code "47") (name "unconnected-(ME605-Pad1)") (class "Default")
      (node (ref "ME605") (pin "1") (pinfunction "1_1") (pintype "passive"))
    )
    (net (code "48") (name "unconnected-(ME605-Pad2)") (class "Default")
      (node (ref "ME605") (pin "2") (pinfunction "2_2") (pintype "passive"))
    )
    (net (code "49") (name "unconnected-(ME606-Pad1)") (class "Default")
      (node (ref "ME606") (pin "1") (pinfunction "1_1") (pintype "passive"))
    )
    (net (code "50") (name "unconnected-(ME606-Pad2)") (class "Default")
      (node (ref "ME606") (pin "2") (pinfunction "2_2") (pintype "passive"))
    )
    (net (code "51") (name "unconnected-(ME607-Pad1)") (class "Default")
      (node (ref "ME607") (pin "1") (pinfunction "1_1") (pintype "passive"))
    )
    (net (code "52") (name "unconnected-(ME607-Pad2)") (class "Default")
      (node (ref "ME607") (pin "2") (pinfunction "2_2") (pintype "passive"))
    )
    (net (code "53") (name "unconnected-(ME608-Pad1)") (class "Default")
      (node (ref "ME608") (pin "1") (pinfunction "1_1") (pintype "passive"))
    )
    (net (code "54") (name "unconnected-(ME608-Pad2)") (class "Default")
      (node (ref "ME608") (pin "2") (pinfunction "2_2") (pintype "passive"))
    )
    (net (code "55") (name "unconnected-(ME609-Pad1)") (class "Default")
      (node (ref "ME609") (pin "1") (pinfunction "1_1") (pintype "passive"))
    )
    (net (code "56") (name "unconnected-(ME609-Pad2)") (class "Default")
      (node (ref "ME609") (pin "2") (pinfunction "2_2") (pintype "passive"))
    )
  )
)
